# GPIO.net
KiCad netlist of a schematic drawn in Altium Designer
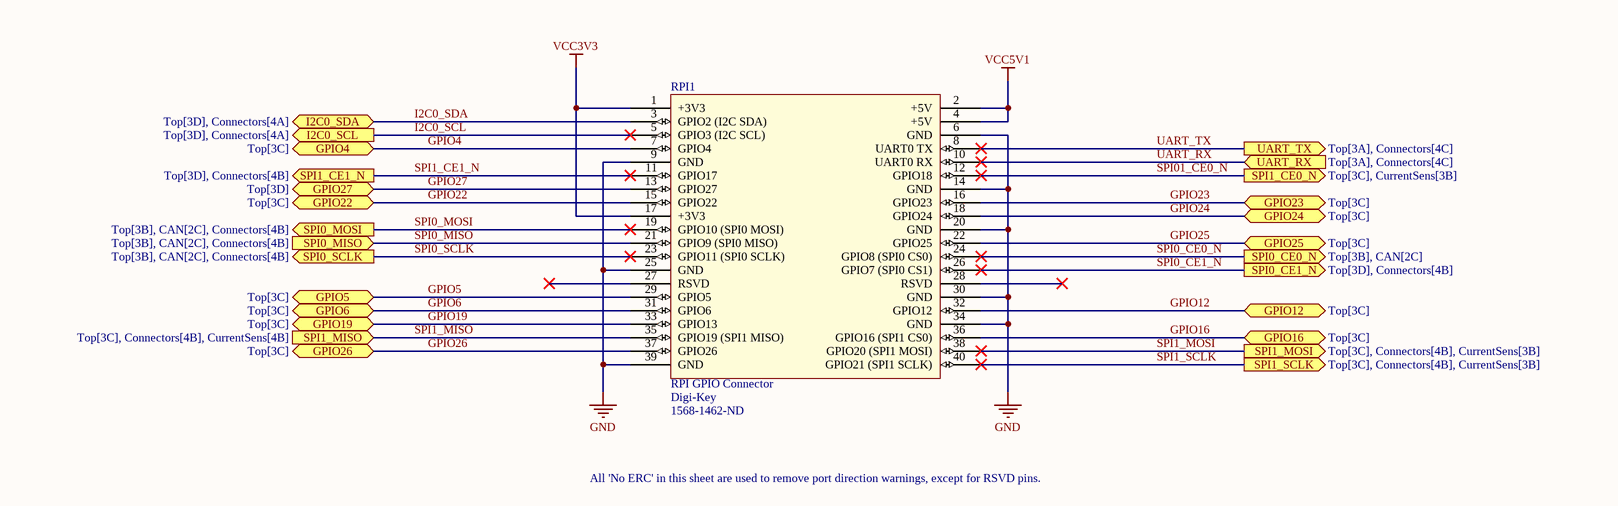
[diagram p0: GPIO.SchDoc]

(export (version "E")
  (design (tool "Eeschema 10.0.6"))
  (components
    (comp (ref "RPI1")
      (value "RPI GPIO Connector")
      (footprint "rpi")
      (description "GPIO Header for Raspberry Pi A+/B+/Pi 2/Pi 3 - 2x20")
      (fields
        (field (name "MANUFACTURER") "SparkFun Electronics")
        (field (name "MANUFACTURER PART NUMBER") "PRT-14017")
        (field (name "SUPPLIER 1") "Digi-Key")
        (field (name "SUPPLIER PART NUMBER 1") "1568-1462-ND")
      )
      (libsource (lib "rpi") (part "rpi connector"))
    )
  )
  (nets
    (net (code "1") (name "/GPIO4") (class "Default")
      (node (ref "RPI1") (pin "7") (pinfunction "GPIO4_7") (pintype "bidirectional"))
    )
    (net (code "2") (name "/GPIO5") (class "Default")
      (node (ref "RPI1") (pin "29") (pinfunction "GPIO5_29") (pintype "bidirectional"))
    )
    (net (code "3") (name "/GPIO6") (class "Default")
      (node (ref "RPI1") (pin "31") (pinfunction "GPIO6_31") (pintype "bidirectional"))
    )
    (net (code "4") (name "/GPIO12") (class "Default")
      (node (ref "RPI1") (pin "32") (pinfunction "GPIO12_32") (pintype "bidirectional"))
    )
    (net (code "5") (name "/GPIO16") (class "Default")
      (node (ref "RPI1") (pin "36") (pinfunction "GPIO16_(SPI1_CS0)_36") (pintype "bidirectional"))
    )
    (net (code "6") (name "/GPIO19") (class "Default")
      (node (ref "RPI1") (pin "33") (pinfunction "GPIO13_33") (pintype "bidirectional"))
    )
    (net (code "7") (name "/GPIO22") (class "Default")
      (node (ref "RPI1") (pin "15") (pinfunction "GPIO22_15") (pintype "bidirectional"))
    )
    (net (code "8") (name "/GPIO23") (class "Default")
      (node (ref "RPI1") (pin "16") (pinfunction "GPIO23_16") (pintype "bidirectional"))
    )
    (net (code "9") (name "/GPIO24") (class "Default")
      (node (ref "RPI1") (pin "18") (pinfunction "GPIO24_18") (pintype "bidirectional"))
    )
    (net (code "10") (name "/GPIO25") (class "Default")
      (node (ref "RPI1") (pin "22") (pinfunction "GPIO25_22") (pintype "bidirectional"))
    )
    (net (code "11") (name "/GPIO26") (class "Default")
      (node (ref "RPI1") (pin "37") (pinfunction "GPIO26_37") (pintype "bidirectional"))
    )
    (net (code "12") (name "/GPIO27") (class "Default")
      (node (ref "RPI1") (pin "13") (pinfunction "GPIO27_13") (pintype "bidirectional"))
    )
    (net (code "13") (name "/I2C0_SCL") (class "Default")
      (node (ref "RPI1") (pin "5") (pinfunction "GPIO3_(I2C_SCL)_5") (pintype "bidirectional+no_connect"))
    )
    (net (code "14") (name "/I2C0_SDA") (class "Default")
      (node (ref "RPI1") (pin "3") (pinfunction "GPIO2_(I2C_SDA)_3") (pintype "bidirectional"))
    )
    (net (code "15") (name "/SPI0_CE0_N") (class "Default")
      (node (ref "RPI1") (pin "24") (pinfunction "GPIO8_(SPI0_CS0)_24") (pintype "bidirectional+no_connect"))
    )
    (net (code "16") (name "/SPI0_CE1_N") (class "Default")
      (node (ref "RPI1") (pin "26") (pinfunction "GPIO7_(SPI0_CS1)_26") (pintype "bidirectional+no_connect"))
    )
    (net (code "17") (name "/SPI0_MISO") (class "Default")
      (node (ref "RPI1") (pin "21") (pinfunction "GPIO9_(SPI0_MISO)_21") (pintype "bidirectional"))
    )
    (net (code "18") (name "/SPI0_MOSI") (class "Default")
      (node (ref "RPI1") (pin "19") (pinfunction "GPIO10_(SPI0_MOSI)_19") (pintype "bidirectional+no_connect"))
    )
    (net (code "19") (name "/SPI0_SCLK") (class "Default")
      (node (ref "RPI1") (pin "23") (pinfunction "GPIO11_(SPI0_SCLK)_23") (pintype "bidirectional+no_connect"))
    )
    (net (code "20") (name "/SPI01_CE0_N") (class "Default")
      (node (ref "RPI1") (pin "12") (pinfunction "GPIO18_12") (pintype "bidirectional+no_connect"))
    )
    (net (code "21") (name "/SPI1_CE1_N") (class "Default")
      (node (ref "RPI1") (pin "11") (pinfunction "GPIO17_11") (pintype "bidirectional+no_connect"))
    )
    (net (code "22") (name "/SPI1_MISO") (class "Default")
      (node (ref "RPI1") (pin "35") (pinfunction "GPIO19_(SPI1_MISO)_35") (pintype "bidirectional"))
    )
    (net (code "23") (name "/SPI1_MOSI") (class "Default")
      (node (ref "RPI1") (pin "38") (pinfunction "GPIO20_(SPI1_MOSI)_38") (pintype "bidirectional+no_connect"))
    )
    (net (code "24") (name "/SPI1_SCLK") (class "Default")
      (node (ref "RPI1") (pin "40") (pinfunction "GPIO21_(SPI1_SCLK)_40") (pintype "bidirectional+no_connect"))
    )
    (net (code "25") (name "/UART_RX") (class "Default")
      (node (ref "RPI1") (pin "10") (pinfunction "UART0_RX_10") (pintype "bidirectional+no_connect"))
    )
    (net (code "26") (name "/UART_TX") (class "Default")
      (node (ref "RPI1") (pin "8") (pinfunction "UART0_TX_8") (pintype "bidirectional+no_connect"))
    )
    (net (code "27") (name "GND") (class "Default")
      (node (ref "RPI1") (pin "14") (pinfunction "GND_14") (pintype "power_in"))
      (node (ref "RPI1") (pin "20") (pinfunction "GND_20") (pintype "power_in"))
      (node (ref "RPI1") (pin "25") (pinfunction "GND_25") (pintype "power_in"))
      (node (ref "RPI1") (pin "30") (pinfunction "GND_30") (pintype "power_in"))
      (node (ref "RPI1") (pin "34") (pinfunction "GND_34") (pintype "passive"))
      (node (ref "RPI1") (pin "39") (pinfunction "GND_39") (pintype "power_in"))
      (node (ref "RPI1") (pin "6") (pinfunction "GND_6") (pintype "power_in"))
      (node (ref "RPI1") (pin "9") (pinfunction "GND_9") (pintype "power_in"))
    )
    (net (code "28") (name "VCC3V3") (class "Default")
      (node (ref "RPI1") (pin "1") (pinfunction "+3V3_1") (pintype "power_in"))
      (node (ref "RPI1") (pin "17") (pinfunction "+3V3_17") (pintype "power_in"))
    )
    (net (code "29") (name "VCC5V1") (class "Default")
      (node (ref "RPI1") (pin "2") (pinfunction "+5V_2") (pintype "power_in"))
      (node (ref "RPI1") (pin "4") (pinfunction "+5V_4") (pintype "power_in"))
    )
    (net (code "30") (name "unconnected-(RPI1-RSVD-Pad27)") (class "Default")
      (node (ref "RPI1") (pin "27") (pinfunction "RSVD_27") (pintype "passive+no_connect"))
    )
    (net (code "31") (name "unconnected-(RPI1-RSVD-Pad28)") (class "Default")
      (node (ref "RPI1") (pin "28") (pinfunction "RSVD_28") (pintype "passive+no_connect"))
    )
  )
)
